# TinymeshBreakout1.net
KiCad netlist of a schematic drawn in EAGLE
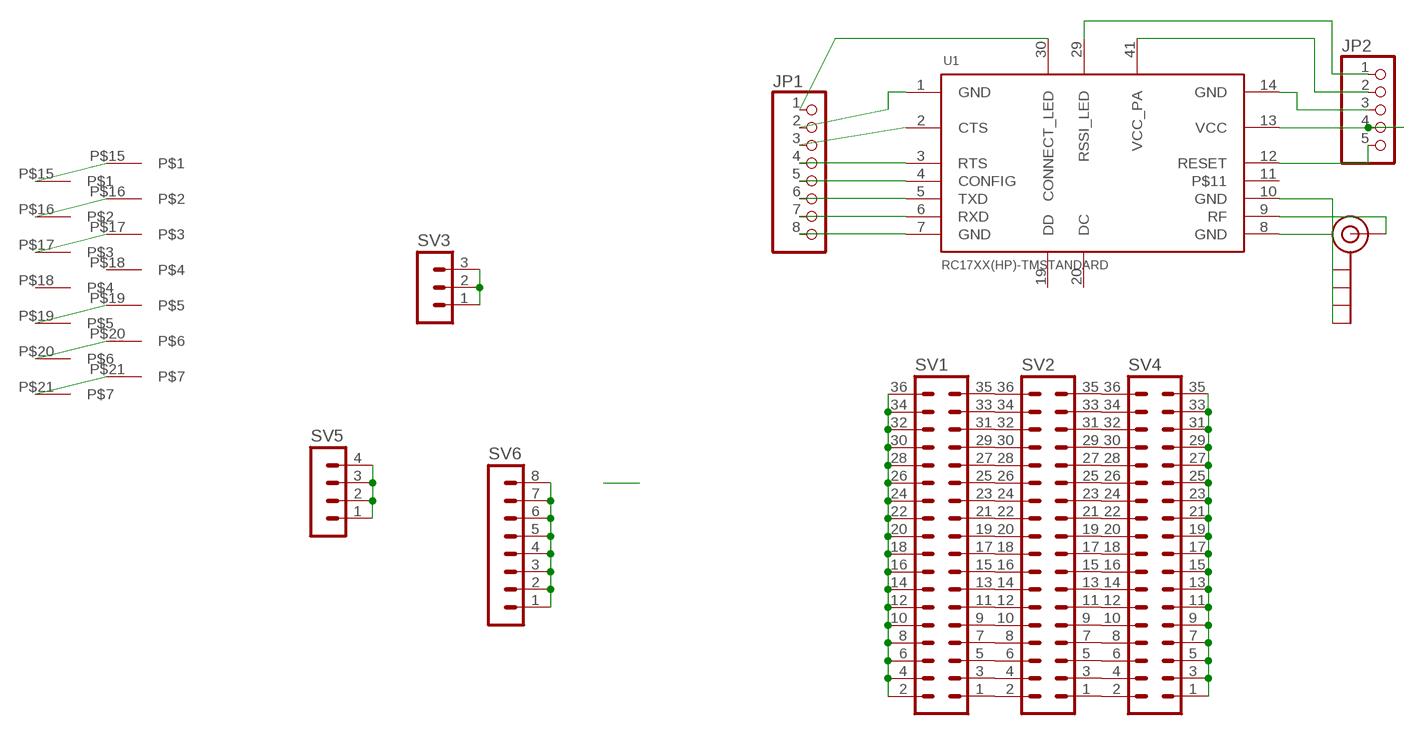
[diagram p0: schematic, sheet 1]

(export (version "E")
  (design (tool "Eeschema 10.0.6"))
  (components
    (comp (ref "J$1")
      (value "SMA_EDGE")
      (footprint "eagle-import:SMA-EDGE")
      (libsource (lib "eagle-import") (part "SMA_EDGE"))
    )
    (comp (ref "JP1")
      (value "PINHD-1X8")
      (footprint "eagle-import:1X08")
      (libsource (lib "eagle-import") (part "PINHD-1X8"))
    )
    (comp (ref "JP2")
      (value "PINHD-1X5")
      (footprint "eagle-import:1X05")
      (libsource (lib "eagle-import") (part "PINHD-1X5"))
    )
    (comp (ref "SV1")
      (value "MA18-2")
      (footprint "eagle-import:MA18-2")
      (libsource (lib "eagle-import") (part "MA18-2"))
    )
    (comp (ref "SV2")
      (value "MA18-2")
      (footprint "eagle-import:MA18-2")
      (libsource (lib "eagle-import") (part "MA18-2"))
    )
    (comp (ref "SV3")
      (value "MA03-1")
      (footprint "eagle-import:MA03-1")
      (libsource (lib "eagle-import") (part "MA03-1"))
    )
    (comp (ref "SV4")
      (value "MA18-2")
      (footprint "eagle-import:MA18-2")
      (libsource (lib "eagle-import") (part "MA18-2"))
    )
    (comp (ref "SV5")
      (value "MA04-1")
      (footprint "eagle-import:MA04-1")
      (libsource (lib "eagle-import") (part "MA04-1"))
    )
    (comp (ref "SV6")
      (value "MA08-1")
      (footprint "eagle-import:MA08-1")
      (libsource (lib "eagle-import") (part "MA08-1"))
    )
    (comp (ref "U$1")
      (value "OEMSRR")
      (footprint "eagle-import:OEMSRR")
      (libsource (lib "eagle-import") (part "OEMSRR"))
    )
    (comp (ref "U$2")
      (value "OEMSRR")
      (footprint "eagle-import:OEMSRR")
      (libsource (lib "eagle-import") (part "OEMSRR"))
    )
    (comp (ref "U1")
      (value "RC17XX(HP)-TMSTANDARD")
      (footprint "eagle-import:RC17XX(HP)-TM")
      (libsource (lib "eagle-import") (part "RC17XX(HP)-TMSTANDARD"))
    )
  )
  (nets
    (net (code "1") (name "/GND") (class "Default")
      (node (ref "J$1") (pin "GND@2") (pinfunction "GND_GND@2") (pintype "bidirectional"))
      (node (ref "J$1") (pin "GND@3") (pinfunction "GND_GND@3") (pintype "bidirectional"))
      (node (ref "JP1") (pin "2") (pinfunction "2_2") (pintype "passive"))
      (node (ref "JP2") (pin "3") (pinfunction "3_3") (pintype "passive"))
      (node (ref "SV1") (pin "10") (pinfunction "10_10") (pintype "passive"))
      (node (ref "SV1") (pin "12") (pinfunction "12_12") (pintype "passive"))
      (node (ref "SV1") (pin "14") (pinfunction "14_14") (pintype "passive"))
      (node (ref "SV1") (pin "16") (pinfunction "16_16") (pintype "passive"))
      (node (ref "SV1") (pin "18") (pinfunction "18_18") (pintype "passive"))
      (node (ref "SV1") (pin "2") (pinfunction "2_2") (pintype "passive"))
      (node (ref "SV1") (pin "20") (pinfunction "20_20") (pintype "passive"))
      (node (ref "SV1") (pin "22") (pinfunction "22_22") (pintype "passive"))
      (node (ref "SV1") (pin "24") (pinfunction "24_24") (pintype "passive"))
      (node (ref "SV1") (pin "26") (pinfunction "26_26") (pintype "passive"))
      (node (ref "SV1") (pin "28") (pinfunction "28_28") (pintype "passive"))
      (node (ref "SV1") (pin "30") (pinfunction "30_30") (pintype "passive"))
      (node (ref "SV1") (pin "32") (pinfunction "32_32") (pintype "passive"))
      (node (ref "SV1") (pin "34") (pinfunction "34_34") (pintype "passive"))
      (node (ref "SV1") (pin "36") (pinfunction "36_36") (pintype "passive"))
      (node (ref "SV1") (pin "4") (pinfunction "4_4") (pintype "passive"))
      (node (ref "SV1") (pin "6") (pinfunction "6_6") (pintype "passive"))
      (node (ref "SV1") (pin "8") (pinfunction "8_8") (pintype "passive"))
      (node (ref "U1") (pin "1") (pinfunction "GND_1") (pintype "power_in"))
      (node (ref "U1") (pin "10") (pinfunction "GND_10") (pintype "power_in"))
      (node (ref "U1") (pin "14") (pinfunction "GND_14") (pintype "power_in"))
      (node (ref "U1") (pin "8") (pinfunction "GND_8") (pintype "power_in"))
    )
    (net (code "2") (name "Net-(J$1-SIGNAL)") (class "Default")
      (node (ref "J$1") (pin "SIG") (pinfunction "SIGNAL_SIG") (pintype "bidirectional"))
      (node (ref "U1") (pin "9") (pinfunction "RF_9") (pintype "bidirectional"))
    )
    (net (code "3") (name "Net-(JP1-Pad8)") (class "Default")
      (node (ref "JP1") (pin "8") (pinfunction "8_8") (pintype "passive"))
      (node (ref "U1") (pin "7") (pinfunction "GND_7") (pintype "power_in"))
    )
    (net (code "4") (name "Net-(SV1-Pad1)") (class "Default")
      (node (ref "SV1") (pin "1") (pinfunction "1_1") (pintype "passive"))
      (node (ref "SV2") (pin "2") (pinfunction "2_2") (pintype "passive"))
    )
    (net (code "5") (name "Net-(SV1-Pad3)") (class "Default")
      (node (ref "SV1") (pin "3") (pinfunction "3_3") (pintype "passive"))
      (node (ref "SV2") (pin "4") (pinfunction "4_4") (pintype "passive"))
    )
    (net (code "6") (name "Net-(SV1-Pad5)") (class "Default")
      (node (ref "SV1") (pin "5") (pinfunction "5_5") (pintype "passive"))
      (node (ref "SV2") (pin "6") (pinfunction "6_6") (pintype "passive"))
    )
    (net (code "7") (name "Net-(SV1-Pad7)") (class "Default")
      (node (ref "SV1") (pin "7") (pinfunction "7_7") (pintype "passive"))
      (node (ref "SV2") (pin "8") (pinfunction "8_8") (pintype "passive"))
    )
    (net (code "8") (name "Net-(SV1-Pad9)") (class "Default")
      (node (ref "SV1") (pin "9") (pinfunction "9_9") (pintype "passive"))
      (node (ref "SV2") (pin "10") (pinfunction "10_10") (pintype "passive"))
    )
    (net (code "9") (name "Net-(SV1-Pad11)") (class "Default")
      (node (ref "SV1") (pin "11") (pinfunction "11_11") (pintype "passive"))
      (node (ref "SV2") (pin "12") (pinfunction "12_12") (pintype "passive"))
    )
    (net (code "10") (name "Net-(SV1-Pad13)") (class "Default")
      (node (ref "SV1") (pin "13") (pinfunction "13_13") (pintype "passive"))
      (node (ref "SV2") (pin "14") (pinfunction "14_14") (pintype "passive"))
    )
    (net (code "11") (name "Net-(SV1-Pad15)") (class "Default")
      (node (ref "SV1") (pin "15") (pinfunction "15_15") (pintype "passive"))
      (node (ref "SV2") (pin "16") (pinfunction "16_16") (pintype "passive"))
    )
    (net (code "12") (name "Net-(SV1-Pad17)") (class "Default")
      (node (ref "SV1") (pin "17") (pinfunction "17_17") (pintype "passive"))
      (node (ref "SV2") (pin "18") (pinfunction "18_18") (pintype "passive"))
    )
    (net (code "13") (name "Net-(SV1-Pad19)") (class "Default")
      (node (ref "SV1") (pin "19") (pinfunction "19_19") (pintype "passive"))
      (node (ref "SV2") (pin "20") (pinfunction "20_20") (pintype "passive"))
    )
    (net (code "14") (name "Net-(SV1-Pad21)") (class "Default")
      (node (ref "SV1") (pin "21") (pinfunction "21_21") (pintype "passive"))
      (node (ref "SV2") (pin "22") (pinfunction "22_22") (pintype "passive"))
    )
    (net (code "15") (name "Net-(SV1-Pad23)") (class "Default")
      (node (ref "SV1") (pin "23") (pinfunction "23_23") (pintype "passive"))
      (node (ref "SV2") (pin "24") (pinfunction "24_24") (pintype "passive"))
    )
    (net (code "16") (name "Net-(SV1-Pad25)") (class "Default")
      (node (ref "SV1") (pin "25") (pinfunction "25_25") (pintype "passive"))
      (node (ref "SV2") (pin "26") (pinfunction "26_26") (pintype "passive"))
    )
    (net (code "17") (name "Net-(SV1-Pad27)") (class "Default")
      (node (ref "SV1") (pin "27") (pinfunction "27_27") (pintype "passive"))
      (node (ref "SV2") (pin "28") (pinfunction "28_28") (pintype "passive"))
    )
    (net (code "18") (name "Net-(SV1-Pad29)") (class "Default")
      (node (ref "SV1") (pin "29") (pinfunction "29_29") (pintype "passive"))
      (node (ref "SV2") (pin "30") (pinfunction "30_30") (pintype "passive"))
    )
    (net (code "19") (name "Net-(SV1-Pad31)") (class "Default")
      (node (ref "SV1") (pin "31") (pinfunction "31_31") (pintype "passive"))
      (node (ref "SV2") (pin "32") (pinfunction "32_32") (pintype "passive"))
    )
    (net (code "20") (name "Net-(SV1-Pad33)") (class "Default")
      (node (ref "SV1") (pin "33") (pinfunction "33_33") (pintype "passive"))
      (node (ref "SV2") (pin "34") (pinfunction "34_34") (pintype "passive"))
    )
    (net (code "21") (name "Net-(SV1-Pad35)") (class "Default")
      (node (ref "SV1") (pin "35") (pinfunction "35_35") (pintype "passive"))
      (node (ref "SV2") (pin "36") (pinfunction "36_36") (pintype "passive"))
    )
    (net (code "22") (name "Net-(SV2-Pad1)") (class "Default")
      (node (ref "SV2") (pin "1") (pinfunction "1_1") (pintype "passive"))
      (node (ref "SV4") (pin "2") (pinfunction "2_2") (pintype "passive"))
    )
    (net (code "23") (name "Net-(SV2-Pad3)") (class "Default")
      (node (ref "SV2") (pin "3") (pinfunction "3_3") (pintype "passive"))
      (node (ref "SV4") (pin "4") (pinfunction "4_4") (pintype "passive"))
    )
    (net (code "24") (name "Net-(SV2-Pad5)") (class "Default")
      (node (ref "SV2") (pin "5") (pinfunction "5_5") (pintype "passive"))
      (node (ref "SV4") (pin "6") (pinfunction "6_6") (pintype "passive"))
    )
    (net (code "25") (name "Net-(SV2-Pad7)") (class "Default")
      (node (ref "SV2") (pin "7") (pinfunction "7_7") (pintype "passive"))
      (node (ref "SV4") (pin "8") (pinfunction "8_8") (pintype "passive"))
    )
    (net (code "26") (name "Net-(SV2-Pad9)") (class "Default")
      (node (ref "SV2") (pin "9") (pinfunction "9_9") (pintype "passive"))
      (node (ref "SV4") (pin "10") (pinfunction "10_10") (pintype "passive"))
    )
    (net (code "27") (name "Net-(SV2-Pad11)") (class "Default")
      (node (ref "SV2") (pin "11") (pinfunction "11_11") (pintype "passive"))
      (node (ref "SV4") (pin "12") (pinfunction "12_12") (pintype "passive"))
    )
    (net (code "28") (name "Net-(SV2-Pad13)") (class "Default")
      (node (ref "SV2") (pin "13") (pinfunction "13_13") (pintype "passive"))
      (node (ref "SV4") (pin "14") (pinfunction "14_14") (pintype "passive"))
    )
    (net (code "29") (name "Net-(SV2-Pad15)") (class "Default")
      (node (ref "SV2") (pin "15") (pinfunction "15_15") (pintype "passive"))
      (node (ref "SV4") (pin "16") (pinfunction "16_16") (pintype "passive"))
    )
    (net (code "30") (name "Net-(SV2-Pad17)") (class "Default")
      (node (ref "SV2") (pin "17") (pinfunction "17_17") (pintype "passive"))
      (node (ref "SV4") (pin "18") (pinfunction "18_18") (pintype "passive"))
    )
    (net (code "31") (name "Net-(SV2-Pad19)") (class "Default")
      (node (ref "SV2") (pin "19") (pinfunction "19_19") (pintype "passive"))
      (node (ref "SV4") (pin "20") (pinfunction "20_20") (pintype "passive"))
    )
    (net (code "32") (name "Net-(SV2-Pad21)") (class "Default")
      (node (ref "SV2") (pin "21") (pinfunction "21_21") (pintype "passive"))
      (node (ref "SV4") (pin "22") (pinfunction "22_22") (pintype "passive"))
    )
    (net (code "33") (name "Net-(SV2-Pad23)") (class "Default")
      (node (ref "SV2") (pin "23") (pinfunction "23_23") (pintype "passive"))
      (node (ref "SV4") (pin "24") (pinfunction "24_24") (pintype "passive"))
    )
    (net (code "34") (name "Net-(SV2-Pad25)") (class "Default")
      (node (ref "SV2") (pin "25") (pinfunction "25_25") (pintype "passive"))
      (node (ref "SV4") (pin "26") (pinfunction "26_26") (pintype "passive"))
    )
    (net (code "35") (name "Net-(SV2-Pad27)") (class "Default")
      (node (ref "SV2") (pin "27") (pinfunction "27_27") (pintype "passive"))
      (node (ref "SV4") (pin "28") (pinfunction "28_28") (pintype "passive"))
    )
    (net (code "36") (name "Net-(SV2-Pad29)") (class "Default")
      (node (ref "SV2") (pin "29") (pinfunction "29_29") (pintype "passive"))
      (node (ref "SV4") (pin "30") (pinfunction "30_30") (pintype "passive"))
    )
    (net (code "37") (name "Net-(SV2-Pad31)") (class "Default")
      (node (ref "SV2") (pin "31") (pinfunction "31_31") (pintype "passive"))
      (node (ref "SV4") (pin "32") (pinfunction "32_32") (pintype "passive"))
    )
    (net (code "38") (name "Net-(SV2-Pad33)") (class "Default")
      (node (ref "SV2") (pin "33") (pinfunction "33_33") (pintype "passive"))
      (node (ref "SV4") (pin "34") (pinfunction "34_34") (pintype "passive"))
    )
    (net (code "39") (name "Net-(SV2-Pad35)") (class "Default")
      (node (ref "SV2") (pin "35") (pinfunction "35_35") (pintype "passive"))
      (node (ref "SV4") (pin "36") (pinfunction "36_36") (pintype "passive"))
    )
    (net (code "40") (name "Net-(SV3-Pad1)") (class "Default")
      (node (ref "SV3") (pin "1") (pinfunction "1_1") (pintype "passive"))
      (node (ref "SV3") (pin "2") (pinfunction "2_2") (pintype "passive"))
      (node (ref "SV3") (pin "3") (pinfunction "3_3") (pintype "passive"))
    )
    (net (code "41") (name "Net-(SV4-Pad1)") (class "Default")
      (node (ref "SV4") (pin "1") (pinfunction "1_1") (pintype "passive"))
      (node (ref "SV4") (pin "11") (pinfunction "11_11") (pintype "passive"))
      (node (ref "SV4") (pin "13") (pinfunction "13_13") (pintype "passive"))
      (node (ref "SV4") (pin "15") (pinfunction "15_15") (pintype "passive"))
      (node (ref "SV4") (pin "17") (pinfunction "17_17") (pintype "passive"))
      (node (ref "SV4") (pin "19") (pinfunction "19_19") (pintype "passive"))
      (node (ref "SV4") (pin "21") (pinfunction "21_21") (pintype "passive"))
      (node (ref "SV4") (pin "23") (pinfunction "23_23") (pintype "passive"))
      (node (ref "SV4") (pin "25") (pinfunction "25_25") (pintype "passive"))
      (node (ref "SV4") (pin "27") (pinfunction "27_27") (pintype "passive"))
      (node (ref "SV4") (pin "29") (pinfunction "29_29") (pintype "passive"))
      (node (ref "SV4") (pin "3") (pinfunction "3_3") (pintype "passive"))
      (node (ref "SV4") (pin "31") (pinfunction "31_31") (pintype "passive"))
      (node (ref "SV4") (pin "33") (pinfunction "33_33") (pintype "passive"))
      (node (ref "SV4") (pin "35") (pinfunction "35_35") (pintype "passive"))
      (node (ref "SV4") (pin "5") (pinfunction "5_5") (pintype "passive"))
      (node (ref "SV4") (pin "7") (pinfunction "7_7") (pintype "passive"))
      (node (ref "SV4") (pin "9") (pinfunction "9_9") (pintype "passive"))
    )
    (net (code "42") (name "Net-(SV5-Pad1)") (class "Default")
      (node (ref "SV5") (pin "1") (pinfunction "1_1") (pintype "passive"))
      (node (ref "SV5") (pin "2") (pinfunction "2_2") (pintype "passive"))
      (node (ref "SV5") (pin "3") (pinfunction "3_3") (pintype "passive"))
      (node (ref "SV5") (pin "4") (pinfunction "4_4") (pintype "passive"))
    )
    (net (code "43") (name "Net-(SV6-Pad1)") (class "Default")
      (node (ref "SV6") (pin "1") (pinfunction "1_1") (pintype "passive"))
      (node (ref "SV6") (pin "2") (pinfunction "2_2") (pintype "passive"))
      (node (ref "SV6") (pin "3") (pinfunction "3_3") (pintype "passive"))
      (node (ref "SV6") (pin "4") (pinfunction "4_4") (pintype "passive"))
      (node (ref "SV6") (pin "5") (pinfunction "5_5") (pintype "passive"))
      (node (ref "SV6") (pin "6") (pinfunction "6_6") (pintype "passive"))
      (node (ref "SV6") (pin "7") (pinfunction "7_7") (pintype "passive"))
      (node (ref "SV6") (pin "8") (pinfunction "8_8") (pintype "passive"))
    )
    (net (code "44") (name "Net-(U$1-P$1)") (class "Default")
      (node (ref "U$1") (pin "P$15") (pinfunction "P$1_P$15") (pintype "bidirectional"))
      (node (ref "U$2") (pin "P$15") (pinfunction "P$1_P$15") (pintype "bidirectional"))
    )
    (net (code "45") (name "Net-(U$1-P$2)") (class "Default")
      (node (ref "U$1") (pin "P$16") (pinfunction "P$2_P$16") (pintype "bidirectional"))
      (node (ref "U$2") (pin "P$16") (pinfunction "P$2_P$16") (pintype "bidirectional"))
    )
    (net (code "46") (name "Net-(U$1-P$3)") (class "Default")
      (node (ref "U$1") (pin "P$17") (pinfunction "P$3_P$17") (pintype "bidirectional"))
      (node (ref "U$2") (pin "P$17") (pinfunction "P$3_P$17") (pintype "bidirectional"))
    )
    (net (code "47") (name "Net-(U$1-P$5)") (class "Default")
      (node (ref "U$1") (pin "P$19") (pinfunction "P$5_P$19") (pintype "bidirectional"))
      (node (ref "U$2") (pin "P$19") (pinfunction "P$5_P$19") (pintype "bidirectional"))
    )
    (net (code "48") (name "Net-(U$1-P$6)") (class "Default")
      (node (ref "U$1") (pin "P$20") (pinfunction "P$6_P$20") (pintype "bidirectional"))
      (node (ref "U$2") (pin "P$20") (pinfunction "P$6_P$20") (pintype "bidirectional"))
    )
    (net (code "49") (name "Net-(U$1-P$7)") (class "Default")
      (node (ref "U$1") (pin "P$21") (pinfunction "P$7_P$21") (pintype "bidirectional"))
      (node (ref "U$2") (pin "P$21") (pinfunction "P$7_P$21") (pintype "bidirectional"))
    )
    (net (code "50") (name "Net-(U1-CONFIG)") (class "Default")
      (node (ref "JP1") (pin "5") (pinfunction "5_5") (pintype "passive"))
      (node (ref "U1") (pin "4") (pinfunction "CONFIG_4") (pintype "input"))
    )
    (net (code "51") (name "Net-(U1-CONNECT_LED)") (class "Default")
      (node (ref "JP1") (pin "1") (pinfunction "1_1") (pintype "passive"))
      (node (ref "U1") (pin "30") (pinfunction "CONNECT_LED_30") (pintype "output"))
    )
    (net (code "52") (name "Net-(U1-CTS)") (class "Default")
      (node (ref "JP1") (pin "3") (pinfunction "3_3") (pintype "passive"))
      (node (ref "U1") (pin "2") (pinfunction "CTS_2") (pintype "output"))
    )
    (net (code "53") (name "Net-(U1-RESET)") (class "Default")
      (node (ref "JP2") (pin "5") (pinfunction "5_5") (pintype "passive"))
      (node (ref "U1") (pin "12") (pinfunction "RESET_12") (pintype "input"))
    )
    (net (code "54") (name "Net-(U1-RSSI_LED)") (class "Default")
      (node (ref "JP2") (pin "1") (pinfunction "1_1") (pintype "passive"))
      (node (ref "U1") (pin "29") (pinfunction "RSSI_LED_29") (pintype "output"))
    )
    (net (code "55") (name "Net-(U1-RTS)") (class "Default")
      (node (ref "JP1") (pin "4") (pinfunction "4_4") (pintype "passive"))
      (node (ref "U1") (pin "3") (pinfunction "RTS_3") (pintype "input"))
    )
    (net (code "56") (name "Net-(U1-RXD)") (class "Default")
      (node (ref "JP1") (pin "7") (pinfunction "7_7") (pintype "passive"))
      (node (ref "U1") (pin "6") (pinfunction "RXD_6") (pintype "input"))
    )
    (net (code "57") (name "Net-(U1-TXD)") (class "Default")
      (node (ref "JP1") (pin "6") (pinfunction "6_6") (pintype "passive"))
      (node (ref "U1") (pin "5") (pinfunction "TXD_5") (pintype "output"))
    )
    (net (code "58") (name "Net-(U1-VCC)") (class "Default")
      (node (ref "JP2") (pin "4") (pinfunction "4_4") (pintype "passive"))
      (node (ref "U1") (pin "13") (pinfunction "VCC_13") (pintype "power_in"))
    )
    (net (code "59") (name "Net-(U1-VCC_PA)") (class "Default")
      (node (ref "JP2") (pin "2") (pinfunction "2_2") (pintype "passive"))
      (node (ref "U1") (pin "41") (pinfunction "VCC_PA_41") (pintype "power_in"))
    )
    (net (code "60") (name "unconnected-(J$1-GND-PadGND@0)") (class "Default")
      (node (ref "J$1") (pin "GND@0") (pinfunction "GND_GND@0") (pintype "bidirectional"))
    )
    (net (code "61") (name "unconnected-(J$1-GND-PadGND@1)") (class "Default")
      (node (ref "J$1") (pin "GND@1") (pinfunction "GND_GND@1") (pintype "bidirectional"))
    )
    (net (code "62") (name "unconnected-(U$1-P$4-PadP$18)") (class "Default")
      (node (ref "U$1") (pin "P$18") (pinfunction "P$4_P$18") (pintype "bidirectional"))
    )
    (net (code "63") (name "unconnected-(U$2-P$4-PadP$18)") (class "Default")
      (node (ref "U$2") (pin "P$18") (pinfunction "P$4_P$18") (pintype "bidirectional"))
    )
    (net (code "64") (name "unconnected-(U1-DC-Pad20)") (class "Default")
      (node (ref "U1") (pin "20") (pinfunction "DC_20") (pintype "bidirectional"))
    )
    (net (code "65") (name "unconnected-(U1-DD-Pad19)") (class "Default")
      (node (ref "U1") (pin "19") (pinfunction "DD_19") (pintype "bidirectional"))
    )
    (net (code "66") (name "unconnected-(U1-P$11-Pad11)") (class "Default")
      (node (ref "U1") (pin "11") (pinfunction "P$11_11") (pintype "bidirectional"))
    )
  )
)
